# Analog_Input.net
KiCad netlist of a schematic drawn in Altium Designer
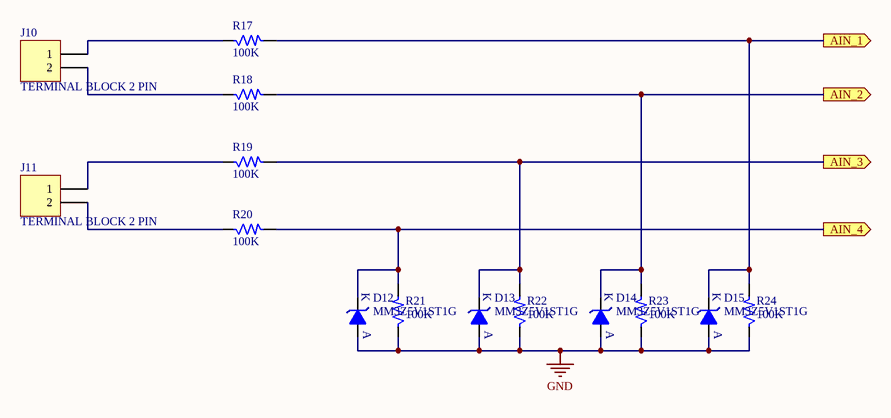
[diagram p0: Analog Input.SchDoc]

(export (version "E")
  (design (tool "Eeschema 10.0.6"))
  (components
    (comp (ref "D12")
      (value "MM3Z5V1ST1G")
      (footprint "DIO_SOD-323F")
      (description "Zener Diode 5.1V 300mW ±2% Surface Mount SOD-323")
      (fields (field (name "MANUFACTURER") "Vishay Semiconductors"))
      (libsource (lib "ESTEEMPCBLIB") (part "DIO-Z_5.1V-300mW-SOD323"))
    )
    (comp (ref "D13")
      (value "MM3Z5V1ST1G")
      (footprint "DIO_SOD-323F")
      (description "Zener Diode 5.1V 300mW ±2% Surface Mount SOD-323")
      (fields (field (name "MANUFACTURER") "Vishay Semiconductors"))
      (libsource (lib "ESTEEMPCBLIB") (part "DIO-Z_5.1V-300mW-SOD323"))
    )
    (comp (ref "D14")
      (value "MM3Z5V1ST1G")
      (footprint "DIO_SOD-323F")
      (description "Zener Diode 5.1V 300mW ±2% Surface Mount SOD-323")
      (fields (field (name "MANUFACTURER") "Vishay Semiconductors"))
      (libsource (lib "ESTEEMPCBLIB") (part "DIO-Z_5.1V-300mW-SOD323"))
    )
    (comp (ref "D15")
      (value "MM3Z5V1ST1G")
      (footprint "DIO_SOD-323F")
      (description "Zener Diode 5.1V 300mW ±2% Surface Mount SOD-323")
      (fields (field (name "MANUFACTURER") "Vishay Semiconductors"))
      (libsource (lib "ESTEEMPCBLIB") (part "DIO-Z_5.1V-300mW-SOD323"))
    )
    (comp (ref "J10")
      (value "TERMINAL BLOCK 2 PIN")
      (footprint "CON2_P196_1729128_TH_ST")
      (description "2 Pins, 1 Row 5mm Pitch, straight Connector, male")
      (fields
        (field (name "MANUFACTURER") "Phoenix Contact")
        (field (name "MANUFACTURER PART NUMBER") "MKDSN1,5/2")
      )
      (libsource (lib "ESTEEMPCBLIB") (part "CON-TB_2X1-196-ST-TH"))
    )
    (comp (ref "J11")
      (value "TERMINAL BLOCK 2 PIN")
      (footprint "CON2_P196_1729128_TH_ST")
      (description "2 Pins, 1 Row 5mm Pitch, straight Connector, male")
      (fields
        (field (name "MANUFACTURER") "Phoenix Contact")
        (field (name "MANUFACTURER PART NUMBER") "MKDSN1,5/2")
      )
      (libsource (lib "ESTEEMPCBLIB") (part "CON-TB_2X1-196-ST-TH"))
    )
    (comp (ref "R17")
      (value "100K")
      (footprint "RES_0805")
      (description "100 kOhms ±1% 0.125W, 1/8W Chip Resistor 0805 (2012 Metric) Automotive AEC-Q200 Thick Film")
      (fields (field (name "MANUFACTURER") "Walsin") (field (name "MANUFACTURER PART NUMBER") "WR08X1003FTL"))
      (libsource (lib "ESTEEMPCBLIB") (part "RES_100K-0.125W-1%-0805"))
    )
    (comp (ref "R18")
      (value "100K")
      (footprint "RES_0805")
      (description "100 kOhms ±1% 0.125W, 1/8W Chip Resistor 0805 (2012 Metric) Automotive AEC-Q200 Thick Film")
      (fields (field (name "MANUFACTURER") "Walsin") (field (name "MANUFACTURER PART NUMBER") "WR08X1003FTL"))
      (libsource (lib "ESTEEMPCBLIB") (part "RES_100K-0.125W-1%-0805"))
    )
    (comp (ref "R19")
      (value "100K")
      (footprint "RES_0805")
      (description "100 kOhms ±1% 0.125W, 1/8W Chip Resistor 0805 (2012 Metric) Automotive AEC-Q200 Thick Film")
      (fields (field (name "MANUFACTURER") "Walsin") (field (name "MANUFACTURER PART NUMBER") "WR08X1003FTL"))
      (libsource (lib "ESTEEMPCBLIB") (part "RES_100K-0.125W-1%-0805"))
    )
    (comp (ref "R20")
      (value "100K")
      (footprint "RES_0805")
      (description "100 kOhms ±1% 0.125W, 1/8W Chip Resistor 0805 (2012 Metric) Automotive AEC-Q200 Thick Film")
      (fields (field (name "MANUFACTURER") "Walsin") (field (name "MANUFACTURER PART NUMBER") "WR08X1003FTL"))
      (libsource (lib "ESTEEMPCBLIB") (part "RES_100K-0.125W-1%-0805"))
    )
    (comp (ref "R21")
      (value "100K")
      (footprint "RES_0805")
      (description "100 kOhms ±1% 0.125W, 1/8W Chip Resistor 0805 (2012 Metric) Automotive AEC-Q200 Thick Film")
      (fields (field (name "MANUFACTURER") "Walsin") (field (name "MANUFACTURER PART NUMBER") "WR08X1003FTL"))
      (libsource (lib "ESTEEMPCBLIB") (part "RES_100K-0.125W-1%-0805"))
    )
    (comp (ref "R22")
      (value "100K")
      (footprint "RES_0805")
      (description "100 kOhms ±1% 0.125W, 1/8W Chip Resistor 0805 (2012 Metric) Automotive AEC-Q200 Thick Film")
      (fields (field (name "MANUFACTURER") "Walsin") (field (name "MANUFACTURER PART NUMBER") "WR08X1003FTL"))
      (libsource (lib "ESTEEMPCBLIB") (part "RES_100K-0.125W-1%-0805"))
    )
    (comp (ref "R23")
      (value "100K")
      (footprint "RES_0805")
      (description "100 kOhms ±1% 0.125W, 1/8W Chip Resistor 0805 (2012 Metric) Automotive AEC-Q200 Thick Film")
      (fields (field (name "MANUFACTURER") "Walsin") (field (name "MANUFACTURER PART NUMBER") "WR08X1003FTL"))
      (libsource (lib "ESTEEMPCBLIB") (part "RES_100K-0.125W-1%-0805"))
    )
    (comp (ref "R24")
      (value "100K")
      (footprint "RES_0805")
      (description "100 kOhms ±1% 0.125W, 1/8W Chip Resistor 0805 (2012 Metric) Automotive AEC-Q200 Thick Film")
      (fields (field (name "MANUFACTURER") "Walsin") (field (name "MANUFACTURER PART NUMBER") "WR08X1003FTL"))
      (libsource (lib "ESTEEMPCBLIB") (part "RES_100K-0.125W-1%-0805"))
    )
  )
  (nets
    (net (code "1") (name "/AIN_1") (class "Default")
      (node (ref "D15") (pin "K") (pinfunction "K_K") (pintype "passive"))
      (node (ref "R17") (pin "2") (pinfunction "2_2") (pintype "passive"))
      (node (ref "R24") (pin "2") (pinfunction "2_2") (pintype "passive"))
    )
    (net (code "2") (name "/AIN_2") (class "Default")
      (node (ref "D14") (pin "K") (pinfunction "K_K") (pintype "passive"))
      (node (ref "R18") (pin "2") (pinfunction "2_2") (pintype "passive"))
      (node (ref "R23") (pin "2") (pinfunction "2_2") (pintype "passive"))
    )
    (net (code "3") (name "/AIN_3") (class "Default")
      (node (ref "D13") (pin "K") (pinfunction "K_K") (pintype "passive"))
      (node (ref "R19") (pin "2") (pinfunction "2_2") (pintype "passive"))
      (node (ref "R22") (pin "2") (pinfunction "2_2") (pintype "passive"))
    )
    (net (code "4") (name "/AIN_4") (class "Default")
      (node (ref "D12") (pin "K") (pinfunction "K_K") (pintype "passive"))
      (node (ref "R20") (pin "2") (pinfunction "2_2") (pintype "passive"))
      (node (ref "R21") (pin "2") (pinfunction "2_2") (pintype "passive"))
    )
    (net (code "5") (name "GND") (class "Default")
      (node (ref "D12") (pin "A") (pinfunction "A_A") (pintype "passive"))
      (node (ref "D13") (pin "A") (pinfunction "A_A") (pintype "passive"))
      (node (ref "D14") (pin "A") (pinfunction "A_A") (pintype "passive"))
      (node (ref "D15") (pin "A") (pinfunction "A_A") (pintype "passive"))
      (node (ref "R21") (pin "1") (pinfunction "1_1") (pintype "passive"))
      (node (ref "R22") (pin "1") (pinfunction "1_1") (pintype "passive"))
      (node (ref "R23") (pin "1") (pinfunction "1_1") (pintype "passive"))
      (node (ref "R24") (pin "1") (pinfunction "1_1") (pintype "passive"))
    )
    (net (code "6") (name "Net-(J10-Pad1)") (class "Default")
      (node (ref "J10") (pin "1") (pinfunction "1_1") (pintype "passive"))
      (node (ref "R17") (pin "1") (pinfunction "1_1") (pintype "passive"))
    )
    (net (code "7") (name "Net-(J10-Pad2)") (class "Default")
      (node (ref "J10") (pin "2") (pinfunction "2_2") (pintype "passive"))
      (node (ref "R18") (pin "1") (pinfunction "1_1") (pintype "passive"))
    )
    (net (code "8") (name "Net-(J11-Pad1)") (class "Default")
      (node (ref "J11") (pin "1") (pinfunction "1_1") (pintype "passive"))
      (node (ref "R19") (pin "1") (pinfunction "1_1") (pintype "passive"))
    )
    (net (code "9") (name "Net-(J11-Pad2)") (class "Default")
      (node (ref "J11") (pin "2") (pinfunction "2_2") (pintype "passive"))
      (node (ref "R20") (pin "1") (pinfunction "1_1") (pintype "passive"))
    )
  )
)
